# supply1.net
KiCad netlist of a schematic drawn in Altium Designer
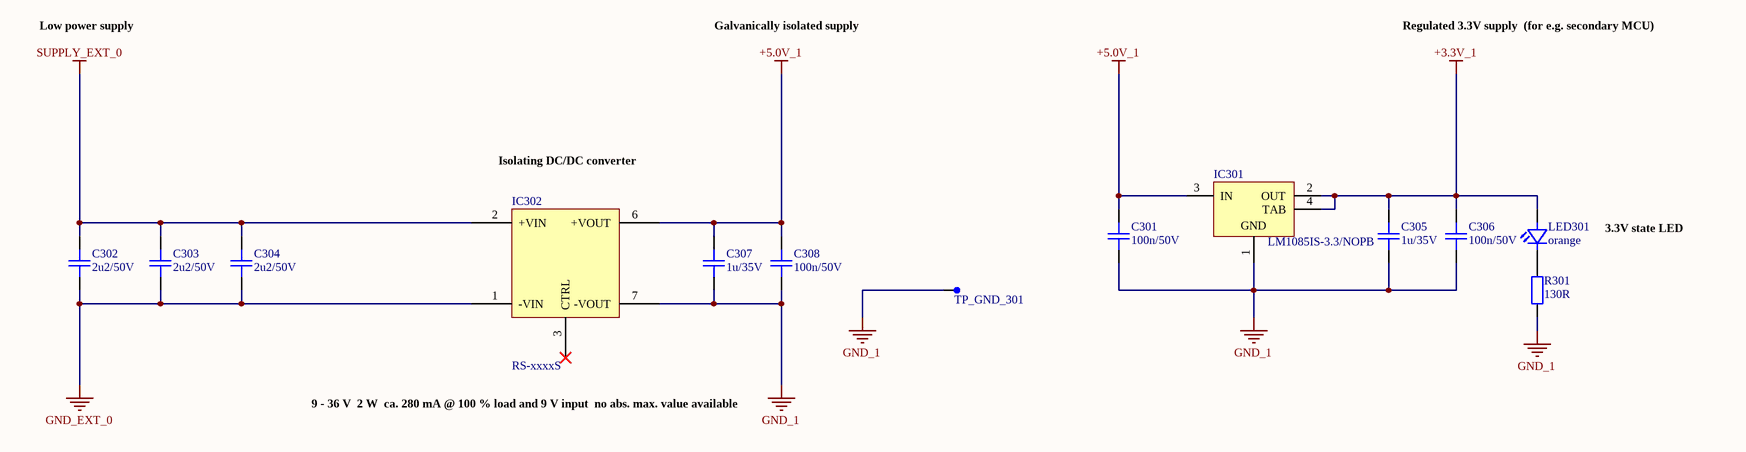
[diagram p0: supply1.SchDoc]

(export (version "E")
  (design (tool "Eeschema 10.0.6"))
  (components
    (comp (ref "C301")
      (value "100n/50V")
      (footprint "CAPC1608X08N")
      (description "MLCC")
      (fields (field (name "PART NUMBER") "gen_C_ceramic_100n_50V_X7R_0603"))
      (libsource (lib "OE750") (part "C"))
    )
    (comp (ref "C302")
      (value "2u2/50V")
      (footprint "CAPC2012X14N")
      (description "MLCC")
      (fields (field (name "PART NUMBER") "gen_C_ceramic_2u2_50V_X7R_0805"))
      (libsource (lib "OE750") (part "C"))
    )
    (comp (ref "C303")
      (value "2u2/50V")
      (footprint "CAPC2012X14N")
      (description "MLCC")
      (fields (field (name "PART NUMBER") "gen_C_ceramic_2u2_50V_X7R_0805"))
      (libsource (lib "OE750") (part "C"))
    )
    (comp (ref "C304")
      (value "2u2/50V")
      (footprint "CAPC2012X14N")
      (description "MLCC")
      (fields (field (name "PART NUMBER") "gen_C_ceramic_2u2_50V_X7R_0805"))
      (libsource (lib "OE750") (part "C"))
    )
    (comp (ref "C305")
      (value "1u/35V")
      (footprint "CAPC1608X08N")
      (description "MLCC")
      (fields (field (name "PART NUMBER") "gen_C_ceramic_1u_35V_X7R_0603"))
      (libsource (lib "OE750") (part "C"))
    )
    (comp (ref "C306")
      (value "100n/50V")
      (footprint "CAPC1608X08N")
      (description "MLCC")
      (fields (field (name "PART NUMBER") "gen_C_ceramic_100n_50V_X7R_0603"))
      (libsource (lib "OE750") (part "C"))
    )
    (comp (ref "C307")
      (value "1u/35V")
      (footprint "CAPC1608X08N")
      (description "MLCC")
      (fields (field (name "PART NUMBER") "gen_C_ceramic_1u_35V_X7R_0603"))
      (libsource (lib "OE750") (part "C"))
    )
    (comp (ref "C308")
      (value "100n/50V")
      (footprint "CAPC1608X08N")
      (description "MLCC")
      (fields (field (name "PART NUMBER") "gen_C_ceramic_100n_50V_X7R_0603"))
      (libsource (lib "OE750") (part "C"))
    )
    (comp (ref "IC301")
      (value "LM1085IS-3.3/NOPB")
      (footprint "KTT0003B_N")
      (description "3A Low Dropout Positive Regulators, 3-pin TO-263, Pb-Free")
      (fields (field (name "MANUFACTURER") "Texas Instruments"))
      (libsource (lib "Altium Content Vault") (part "PM-REG-LM1086-SOT4"))
    )
    (comp (ref "IC302")
      (value "RS-xxxxS")
      (footprint "RECOM_RS-S_D")
      (description "Isolating DC/DC Converter")
      (fields (field (name "PART NUMBER") "Recom_RS-2405SZ/H3") (field (name "MANUFACTURER") "Recom"))
      (libsource (lib "OE750") (part "RS-xxxxS"))
    )
    (comp (ref "LED301")
      (value "orange")
      (footprint "LEDC1608X07N")
      (description "LED")
      (fields (field (name "PART NUMBER") "gen_LED_0603_orange"))
      (libsource (lib "OE750") (part "D_LED"))
    )
    (comp (ref "R301")
      (value "130R")
      (footprint "RESC1608X05N")
      (description "SMD Resistor 130R 0603")
      (fields (field (name "PART NUMBER") "gen_R_130R_0603") (field (name "TOLERANCE") "1%"))
      (libsource (lib "OE750") (part "R"))
    )
    (comp (ref "TP_GND_301")
      (value "Testpoint_Round")
      (footprint "Testpoint_D1V")
      (description "Testpoint, Via, round")
      (fields (field (name "PART NUMBER") "Testpoint_Round_Via"))
      (libsource (lib "OE750") (part "Testpoint_Round"))
    )
  )
  (nets
    (net (code "1") (name "+3.3V_1") (class "Default")
      (node (ref "C305") (pin "1") (pinfunction "1_1") (pintype "passive"))
      (node (ref "C306") (pin "1") (pinfunction "1_1") (pintype "passive"))
      (node (ref "IC301") (pin "2") (pinfunction "OUT_2") (pintype "power_in"))
      (node (ref "IC301") (pin "4") (pinfunction "TAB_4") (pintype "power_in"))
      (node (ref "LED301") (pin "2") (pinfunction "A_2") (pintype "passive"))
    )
    (net (code "2") (name "+5.0V_1") (class "Default")
      (node (ref "C301") (pin "1") (pinfunction "1_1") (pintype "passive"))
      (node (ref "C307") (pin "1") (pinfunction "1_1") (pintype "passive"))
      (node (ref "C308") (pin "1") (pinfunction "1_1") (pintype "passive"))
      (node (ref "IC301") (pin "3") (pinfunction "IN_3") (pintype "power_in"))
      (node (ref "IC302") (pin "6") (pinfunction "+VOUT_6") (pintype "power_in"))
    )
    (net (code "3") (name "GND_1") (class "Default")
      (node (ref "C301") (pin "2") (pinfunction "2_2") (pintype "passive"))
      (node (ref "C305") (pin "2") (pinfunction "2_2") (pintype "passive"))
      (node (ref "C306") (pin "2") (pinfunction "2_2") (pintype "passive"))
      (node (ref "C307") (pin "2") (pinfunction "2_2") (pintype "passive"))
      (node (ref "C308") (pin "2") (pinfunction "2_2") (pintype "passive"))
      (node (ref "IC301") (pin "1") (pinfunction "GND_1") (pintype "power_in"))
      (node (ref "IC302") (pin "7") (pinfunction "-VOUT_7") (pintype "power_in"))
      (node (ref "R301") (pin "2") (pinfunction "2_2") (pintype "passive"))
      (node (ref "TP_GND_301") (pin "1") (pinfunction "1_1") (pintype "passive"))
    )
    (net (code "4") (name "GND_EXT_0") (class "Default")
      (node (ref "C302") (pin "2") (pinfunction "2_2") (pintype "passive"))
      (node (ref "C303") (pin "2") (pinfunction "2_2") (pintype "passive"))
      (node (ref "C304") (pin "2") (pinfunction "2_2") (pintype "passive"))
      (node (ref "IC302") (pin "1") (pinfunction "-VIN_1") (pintype "power_in"))
    )
    (net (code "5") (name "Net-(LED301-C)") (class "Default")
      (node (ref "LED301") (pin "1") (pinfunction "C_1") (pintype "passive"))
      (node (ref "R301") (pin "1") (pinfunction "1_1") (pintype "passive"))
    )
    (net (code "6") (name "SUPPLY_EXT_0") (class "Default")
      (node (ref "C302") (pin "1") (pinfunction "1_1") (pintype "passive"))
      (node (ref "C303") (pin "1") (pinfunction "1_1") (pintype "passive"))
      (node (ref "C304") (pin "1") (pinfunction "1_1") (pintype "passive"))
      (node (ref "IC302") (pin "2") (pinfunction "+VIN_2") (pintype "power_in"))
    )
    (net (code "7") (name "unconnected-(IC302-CTRL-Pad3)") (class "Default")
      (node (ref "IC302") (pin "3") (pinfunction "CTRL_3") (pintype "passive+no_connect"))
    )
  )
)
